# Stage_Driver_v7.net
KiCad netlist of a schematic drawn in EAGLE
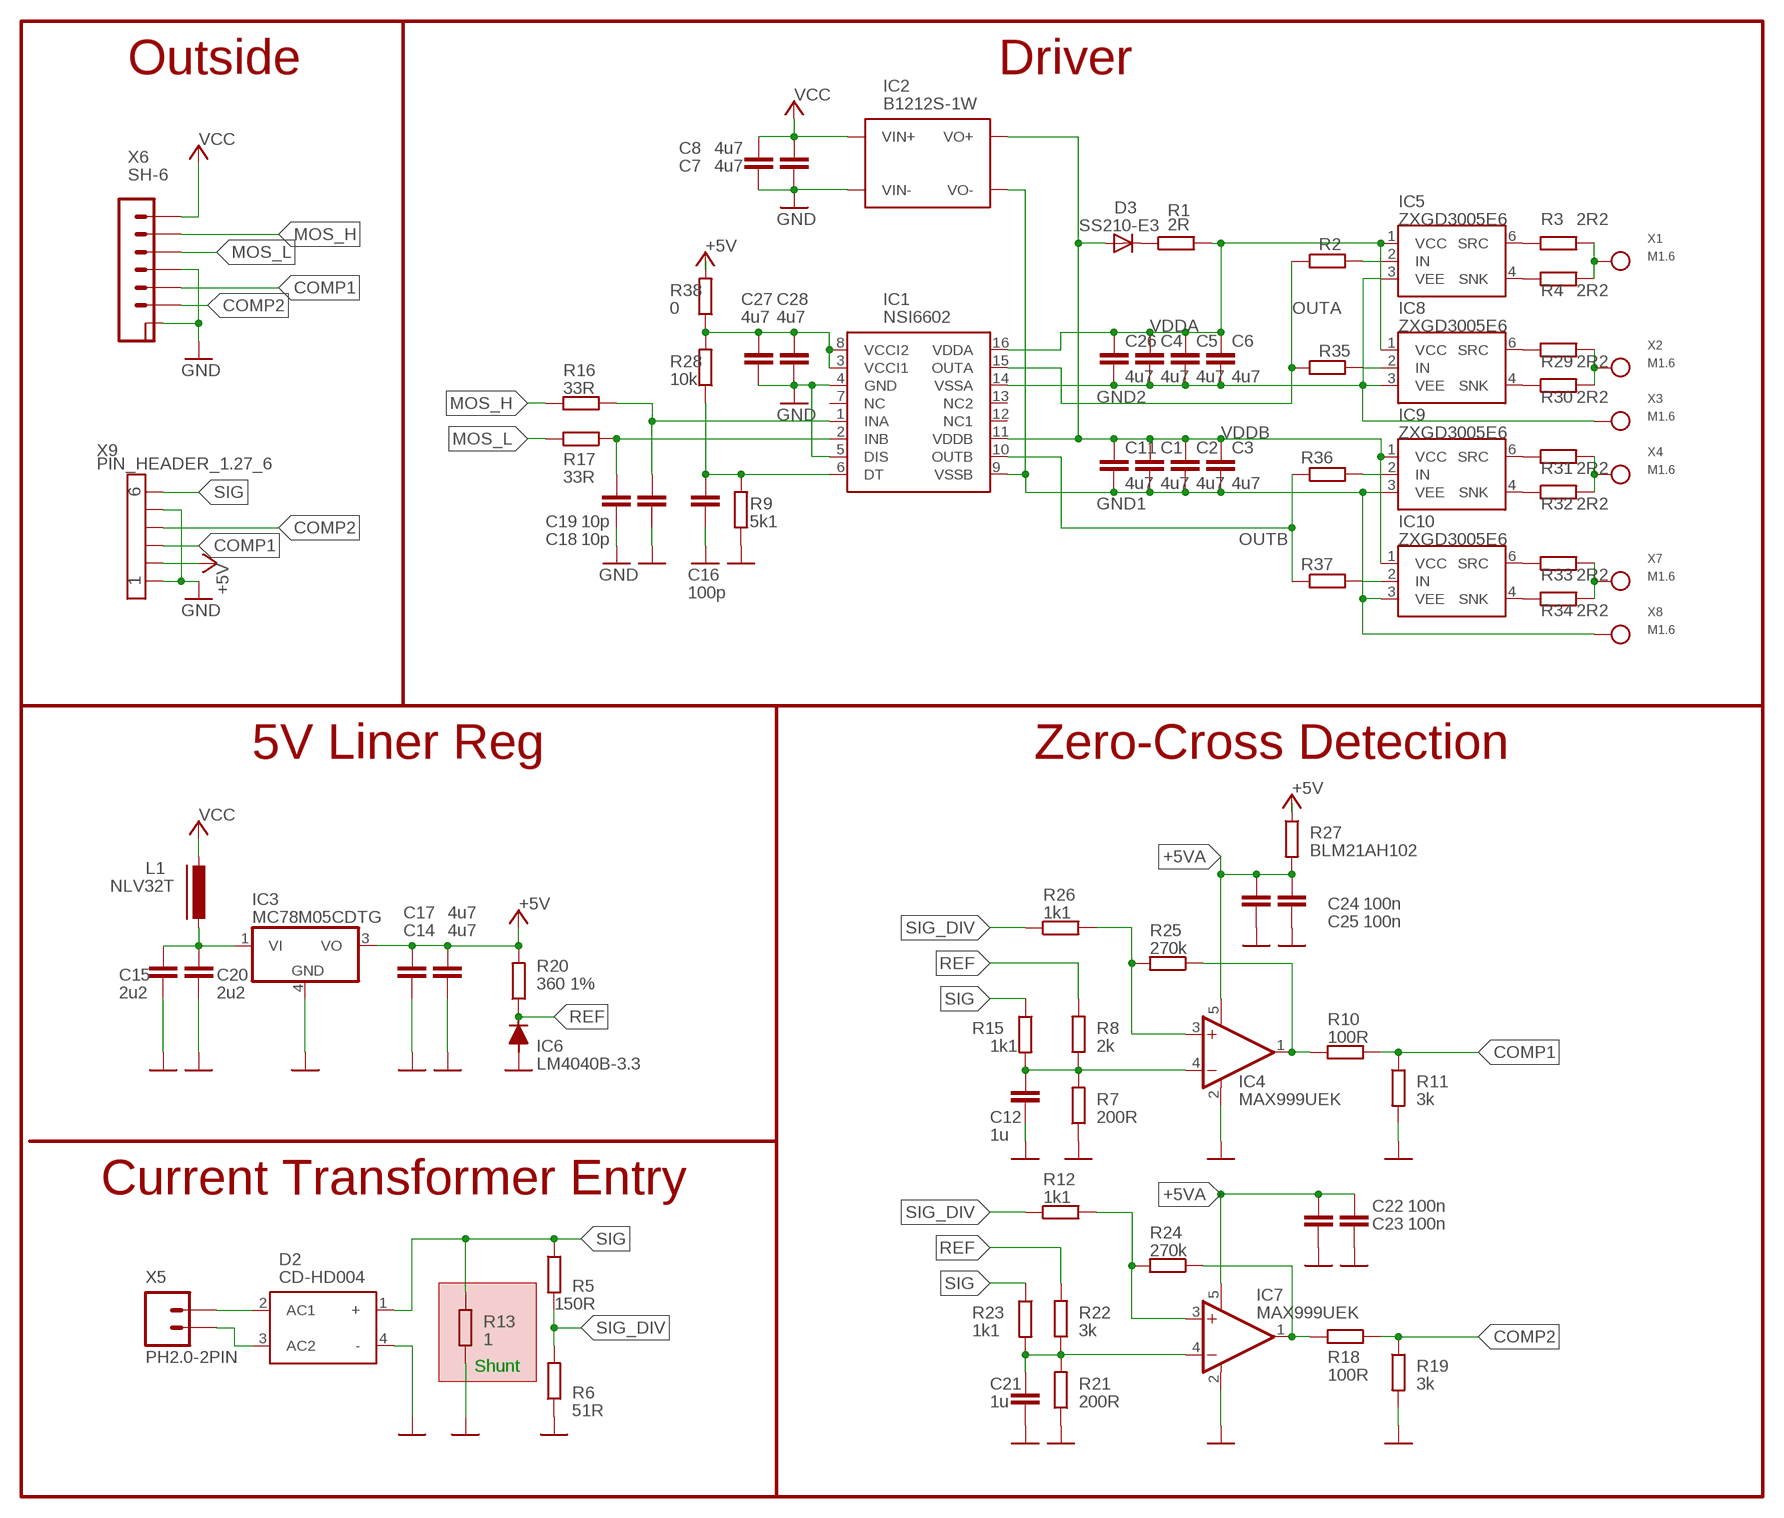
[diagram p0: schematic, sheet 1]

(export (version "E")
  (design (tool "Eeschema 10.0.6"))
  (components
    (comp (ref "C1")
      (value "4u7")
      (footprint "eagle-import:C0805")
      (libsource (lib "eagle-import") (part "C-EUC0805"))
    )
    (comp (ref "C2")
      (value "4u7")
      (footprint "eagle-import:C0805")
      (libsource (lib "eagle-import") (part "C-EUC0805"))
    )
    (comp (ref "C3")
      (value "4u7")
      (footprint "eagle-import:C0805")
      (libsource (lib "eagle-import") (part "C-EUC0805"))
    )
    (comp (ref "C4")
      (value "4u7")
      (footprint "eagle-import:C0805")
      (libsource (lib "eagle-import") (part "C-EUC0805"))
    )
    (comp (ref "C5")
      (value "4u7")
      (footprint "eagle-import:C0805")
      (libsource (lib "eagle-import") (part "C-EUC0805"))
    )
    (comp (ref "C6")
      (value "4u7")
      (footprint "eagle-import:C0805")
      (libsource (lib "eagle-import") (part "C-EUC0805"))
    )
    (comp (ref "C7")
      (value "4u7")
      (footprint "eagle-import:C0805")
      (libsource (lib "eagle-import") (part "C-EUC0805"))
    )
    (comp (ref "C8")
      (value "4u7")
      (footprint "eagle-import:C0805")
      (libsource (lib "eagle-import") (part "C-EUC0805"))
    )
    (comp (ref "C11")
      (value "4u7")
      (footprint "eagle-import:C0805")
      (libsource (lib "eagle-import") (part "C-EUC0805"))
    )
    (comp (ref "C12")
      (value "1u")
      (footprint "eagle-import:C0603")
      (libsource (lib "eagle-import") (part "C-EUC0603"))
    )
    (comp (ref "C14")
      (value "4u7")
      (footprint "eagle-import:C0805")
      (libsource (lib "eagle-import") (part "C-EUC0805"))
    )
    (comp (ref "C15")
      (value "2u2")
      (footprint "eagle-import:C0805")
      (libsource (lib "eagle-import") (part "C-EUC0805"))
    )
    (comp (ref "C16")
      (value "100p")
      (footprint "eagle-import:C0603")
      (libsource (lib "eagle-import") (part "C-EUC0603"))
    )
    (comp (ref "C17")
      (value "4u7")
      (footprint "eagle-import:C0805")
      (libsource (lib "eagle-import") (part "C-EUC0805"))
    )
    (comp (ref "C18")
      (value "10p")
      (footprint "eagle-import:C0603")
      (libsource (lib "eagle-import") (part "C-EUC0603"))
    )
    (comp (ref "C19")
      (value "10p")
      (footprint "eagle-import:C0603")
      (libsource (lib "eagle-import") (part "C-EUC0603"))
    )
    (comp (ref "C20")
      (value "2u2")
      (footprint "eagle-import:C0805")
      (libsource (lib "eagle-import") (part "C-EUC0805"))
    )
    (comp (ref "C21")
      (value "1u")
      (footprint "eagle-import:C0603")
      (libsource (lib "eagle-import") (part "C-EUC0603"))
    )
    (comp (ref "C22")
      (value "100n")
      (footprint "eagle-import:C0603")
      (libsource (lib "eagle-import") (part "C-EUC0603"))
    )
    (comp (ref "C23")
      (value "100n")
      (footprint "eagle-import:C0603")
      (libsource (lib "eagle-import") (part "C-EUC0603"))
    )
    (comp (ref "C24")
      (value "100n")
      (footprint "eagle-import:C0603")
      (libsource (lib "eagle-import") (part "C-EUC0603"))
    )
    (comp (ref "C25")
      (value "100n")
      (footprint "eagle-import:C0603")
      (libsource (lib "eagle-import") (part "C-EUC0603"))
    )
    (comp (ref "C26")
      (value "4u7")
      (footprint "eagle-import:C0805")
      (libsource (lib "eagle-import") (part "C-EUC0805"))
    )
    (comp (ref "C27")
      (value "4u7")
      (footprint "eagle-import:C0603")
      (libsource (lib "eagle-import") (part "C-EUC0603"))
    )
    (comp (ref "C28")
      (value "4u7")
      (footprint "eagle-import:C0603")
      (libsource (lib "eagle-import") (part "C-EUC0603"))
    )
    (comp (ref "D2")
      (value "CD-HD004")
      (footprint "eagle-import:CD-HD0X")
      (libsource (lib "eagle-import") (part "CD-HD004"))
    )
    (comp (ref "D3")
      (value "SS210-E3")
      (footprint "eagle-import:DO-214AA(SMB)")
      (fields
        (field (name "MANUFACTURER_PART_NUMBER") "SS210-E3/5BT")
        (field (name "MOUSER_PART_NUMBER") "625-SS210-E3/5BT")
      )
      (libsource (lib "eagle-import") (part "SS210-E3"))
    )
    (comp (ref "IC1")
      (value "NSI6602")
      (footprint "eagle-import:SOIC16")
      (libsource (lib "eagle-import") (part "NSI6602"))
    )
    (comp (ref "IC2")
      (value "B1212S-1W")
      (footprint "eagle-import:BS-1WR3")
      (libsource (lib "eagle-import") (part "SIM1-XXXX-2"))
    )
    (comp (ref "IC3")
      (value "MC78M05CDTG")
      (footprint "eagle-import:DPACK_3")
      (libsource (lib "eagle-import") (part "MC78M05CDTG"))
    )
    (comp (ref "IC4")
      (value "MAX999UEK")
      (footprint "eagle-import:SOT-23-5")
      (libsource (lib "eagle-import") (part "MAX999UEK"))
    )
    (comp (ref "IC5")
      (value "ZXGD3005E6")
      (footprint "eagle-import:SOT-23-6")
      (libsource (lib "eagle-import") (part "ZXGD3005E6"))
    )
    (comp (ref "IC6")
      (value "LM4040B-3.3")
      (footprint "eagle-import:SOT-23")
      (libsource (lib "eagle-import") (part "LM4040"))
    )
    (comp (ref "IC7")
      (value "MAX999UEK")
      (footprint "eagle-import:SOT-23-5")
      (libsource (lib "eagle-import") (part "MAX999UEK"))
    )
    (comp (ref "IC8")
      (value "ZXGD3005E6")
      (footprint "eagle-import:SOT-23-6")
      (libsource (lib "eagle-import") (part "ZXGD3005E6"))
    )
    (comp (ref "IC9")
      (value "ZXGD3005E6")
      (footprint "eagle-import:SOT-23-6")
      (libsource (lib "eagle-import") (part "ZXGD3005E6"))
    )
    (comp (ref "IC10")
      (value "ZXGD3005E6")
      (footprint "eagle-import:SOT-23-6")
      (libsource (lib "eagle-import") (part "ZXGD3005E6"))
    )
    (comp (ref "L1")
      (value "NLV32T")
      (footprint "eagle-import:NLV32T")
      (libsource (lib "eagle-import") (part "NLV32T"))
    )
    (comp (ref "R1")
      (value "2R")
      (footprint "eagle-import:R1210")
      (libsource (lib "eagle-import") (part "R-EU_R1210"))
    )
    (comp (ref "R2")
      (value "R-EU_R0603")
      (footprint "eagle-import:R0603")
      (libsource (lib "eagle-import") (part "R-EU_R0603"))
    )
    (comp (ref "R3")
      (value "2R2")
      (footprint "eagle-import:R0603")
      (libsource (lib "eagle-import") (part "R-EU_R0603"))
    )
    (comp (ref "R4")
      (value "2R2")
      (footprint "eagle-import:R0603")
      (libsource (lib "eagle-import") (part "R-EU_R0603"))
    )
    (comp (ref "R5")
      (value "150R")
      (footprint "eagle-import:R0805")
      (libsource (lib "eagle-import") (part "R-EU_R0805"))
    )
    (comp (ref "R6")
      (value "51R")
      (footprint "eagle-import:R0805")
      (libsource (lib "eagle-import") (part "R-EU_R0805"))
    )
    (comp (ref "R7")
      (value "200R")
      (footprint "eagle-import:R0603")
      (libsource (lib "eagle-import") (part "R-EU_R0603"))
    )
    (comp (ref "R8")
      (value "2k")
      (footprint "eagle-import:R0603")
      (libsource (lib "eagle-import") (part "R-EU_R0603"))
    )
    (comp (ref "R9")
      (value "5k1")
      (footprint "eagle-import:R0603")
      (libsource (lib "eagle-import") (part "R-EU_R0603"))
    )
    (comp (ref "R10")
      (value "100R")
      (footprint "eagle-import:R0603")
      (libsource (lib "eagle-import") (part "R-EU_R0603"))
    )
    (comp (ref "R11")
      (value "3k")
      (footprint "eagle-import:R0603")
      (libsource (lib "eagle-import") (part "R-EU_R0603"))
    )
    (comp (ref "R12")
      (value "1k1")
      (footprint "eagle-import:R0603")
      (libsource (lib "eagle-import") (part "R-EU_R0603"))
    )
    (comp (ref "R13")
      (value "1")
      (footprint "eagle-import:R1210")
      (libsource (lib "eagle-import") (part "R-EU_R1210"))
    )
    (comp (ref "R15")
      (value "1k1")
      (footprint "eagle-import:R0603")
      (libsource (lib "eagle-import") (part "R-EU_R0603"))
    )
    (comp (ref "R16")
      (value "33R")
      (footprint "eagle-import:R0603")
      (libsource (lib "eagle-import") (part "R-EU_R0603"))
    )
    (comp (ref "R17")
      (value "33R")
      (footprint "eagle-import:R0603")
      (libsource (lib "eagle-import") (part "R-EU_R0603"))
    )
    (comp (ref "R18")
      (value "100R")
      (footprint "eagle-import:R0603")
      (libsource (lib "eagle-import") (part "R-EU_R0603"))
    )
    (comp (ref "R19")
      (value "3k")
      (footprint "eagle-import:R0603")
      (libsource (lib "eagle-import") (part "R-EU_R0603"))
    )
    (comp (ref "R20")
      (value "360 1%")
      (footprint "eagle-import:R0805")
      (libsource (lib "eagle-import") (part "R-EU_R0805"))
    )
    (comp (ref "R21")
      (value "200R")
      (footprint "eagle-import:R0603")
      (libsource (lib "eagle-import") (part "R-EU_R0603"))
    )
    (comp (ref "R22")
      (value "3k")
      (footprint "eagle-import:R0603")
      (libsource (lib "eagle-import") (part "R-EU_R0603"))
    )
    (comp (ref "R23")
      (value "1k1")
      (footprint "eagle-import:R0603")
      (libsource (lib "eagle-import") (part "R-EU_R0603"))
    )
    (comp (ref "R24")
      (value "270k")
      (footprint "eagle-import:R0603")
      (libsource (lib "eagle-import") (part "R-EU_R0603"))
    )
    (comp (ref "R25")
      (value "270k")
      (footprint "eagle-import:R0603")
      (libsource (lib "eagle-import") (part "R-EU_R0603"))
    )
    (comp (ref "R26")
      (value "1k1")
      (footprint "eagle-import:R0603")
      (libsource (lib "eagle-import") (part "R-EU_R0603"))
    )
    (comp (ref "R27")
      (value "BLM21AH102")
      (footprint "eagle-import:R0805")
      (libsource (lib "eagle-import") (part "R-EU_R0805"))
    )
    (comp (ref "R28")
      (value "10k")
      (footprint "eagle-import:R0603")
      (libsource (lib "eagle-import") (part "R-EU_R0603"))
    )
    (comp (ref "R29")
      (value "2R2")
      (footprint "eagle-import:R0603")
      (libsource (lib "eagle-import") (part "R-EU_R0603"))
    )
    (comp (ref "R30")
      (value "2R2")
      (footprint "eagle-import:R0603")
      (libsource (lib "eagle-import") (part "R-EU_R0603"))
    )
    (comp (ref "R31")
      (value "2R2")
      (footprint "eagle-import:R0603")
      (libsource (lib "eagle-import") (part "R-EU_R0603"))
    )
    (comp (ref "R32")
      (value "2R2")
      (footprint "eagle-import:R0603")
      (libsource (lib "eagle-import") (part "R-EU_R0603"))
    )
    (comp (ref "R33")
      (value "2R2")
      (footprint "eagle-import:R0603")
      (libsource (lib "eagle-import") (part "R-EU_R0603"))
    )
    (comp (ref "R34")
      (value "2R2")
      (footprint "eagle-import:R0603")
      (libsource (lib "eagle-import") (part "R-EU_R0603"))
    )
    (comp (ref "R35")
      (value "R-EU_R0603")
      (footprint "eagle-import:R0603")
      (libsource (lib "eagle-import") (part "R-EU_R0603"))
    )
    (comp (ref "R36")
      (value "R-EU_R0603")
      (footprint "eagle-import:R0603")
      (libsource (lib "eagle-import") (part "R-EU_R0603"))
    )
    (comp (ref "R37")
      (value "R-EU_R0603")
      (footprint "eagle-import:R0603")
      (libsource (lib "eagle-import") (part "R-EU_R0603"))
    )
    (comp (ref "R38")
      (value "0")
      (footprint "eagle-import:R0805")
      (libsource (lib "eagle-import") (part "R-EU_R0805"))
    )
    (comp (ref "X1")
      (value "M1.6")
      (footprint "eagle-import:M1.6")
      (libsource (lib "eagle-import") (part "M1.6"))
    )
    (comp (ref "X2")
      (value "M1.6")
      (footprint "eagle-import:M1.6")
      (libsource (lib "eagle-import") (part "M1.6"))
    )
    (comp (ref "X3")
      (value "M1.6")
      (footprint "eagle-import:M1.6")
      (libsource (lib "eagle-import") (part "M1.6"))
    )
    (comp (ref "X4")
      (value "M1.6")
      (footprint "eagle-import:M1.6")
      (libsource (lib "eagle-import") (part "M1.6"))
    )
    (comp (ref "X5")
      (value "PH2.0-2PIN")
      (footprint "eagle-import:PH2.0-2PIN")
      (libsource (lib "eagle-import") (part "PH2.0-2PIN"))
    )
    (comp (ref "X6")
      (value "SH-6")
      (footprint "eagle-import:SH-6")
      (libsource (lib "eagle-import") (part "SH-6"))
    )
    (comp (ref "X7")
      (value "M1.6")
      (footprint "eagle-import:M1.6")
      (libsource (lib "eagle-import") (part "M1.6"))
    )
    (comp (ref "X8")
      (value "M1.6")
      (footprint "eagle-import:M1.6")
      (libsource (lib "eagle-import") (part "M1.6"))
    )
    (comp (ref "X9")
      (value "PIN_HEADER_1.27_6")
      (footprint "eagle-import:PIN_HEADER_1.27_6")
      (libsource (lib "eagle-import") (part "PIN_HEADER_1.27_6"))
    )
  )
  (nets
    (net (code "1") (name "+5V") (class "Default")
      (node (ref "C14") (pin "1") (pinfunction "1_1") (pintype "passive"))
      (node (ref "C17") (pin "1") (pinfunction "1_1") (pintype "passive"))
      (node (ref "IC3") (pin "3") (pinfunction "VO_3") (pintype "passive"))
      (node (ref "R20") (pin "2") (pinfunction "2_2") (pintype "passive"))
      (node (ref "R27") (pin "1") (pinfunction "1_1") (pintype "passive"))
      (node (ref "R38") (pin "2") (pinfunction "2_2") (pintype "passive"))
      (node (ref "X9") (pin "P$2") (pinfunction "P$2_P$2") (pintype "bidirectional"))
    )
    (net (code "2") (name "+5VA") (class "Default")
      (node (ref "C22") (pin "1") (pinfunction "1_1") (pintype "passive"))
      (node (ref "C23") (pin "1") (pinfunction "1_1") (pintype "passive"))
      (node (ref "C24") (pin "1") (pinfunction "1_1") (pintype "passive"))
      (node (ref "C25") (pin "1") (pinfunction "1_1") (pintype "passive"))
      (node (ref "IC4") (pin "5") (pinfunction "V+_5") (pintype "power_in"))
      (node (ref "IC7") (pin "5") (pinfunction "V+_5") (pintype "power_in"))
      (node (ref "R27") (pin "2") (pinfunction "2_2") (pintype "passive"))
    )
    (net (code "3") (name "/GND1") (class "Default")
      (node (ref "C1") (pin "2") (pinfunction "2_2") (pintype "passive"))
      (node (ref "C11") (pin "2") (pinfunction "2_2") (pintype "passive"))
      (node (ref "C2") (pin "2") (pinfunction "2_2") (pintype "passive"))
      (node (ref "C3") (pin "2") (pinfunction "2_2") (pintype "passive"))
      (node (ref "IC1") (pin "9") (pinfunction "VSSB_9") (pintype "bidirectional"))
      (node (ref "IC10") (pin "3") (pinfunction "VEE_3") (pintype "bidirectional"))
      (node (ref "IC2") (pin "P$3") (pinfunction "VO-_P$3") (pintype "bidirectional"))
      (node (ref "IC9") (pin "3") (pinfunction "VEE_3") (pintype "bidirectional"))
      (node (ref "X8") (pin "P$1") (pinfunction "P$1_P$1") (pintype "bidirectional"))
    )
    (net (code "4") (name "/GND2") (class "Default")
      (node (ref "C26") (pin "2") (pinfunction "2_2") (pintype "passive"))
      (node (ref "C4") (pin "2") (pinfunction "2_2") (pintype "passive"))
      (node (ref "C5") (pin "2") (pinfunction "2_2") (pintype "passive"))
      (node (ref "C6") (pin "2") (pinfunction "2_2") (pintype "passive"))
      (node (ref "IC1") (pin "14") (pinfunction "VSSA_14") (pintype "bidirectional"))
      (node (ref "IC5") (pin "3") (pinfunction "VEE_3") (pintype "bidirectional"))
      (node (ref "IC8") (pin "3") (pinfunction "VEE_3") (pintype "bidirectional"))
      (node (ref "X3") (pin "P$1") (pinfunction "P$1_P$1") (pintype "bidirectional"))
    )
    (net (code "5") (name "/OUTA") (class "Default")
      (node (ref "IC1") (pin "15") (pinfunction "OUTA_15") (pintype "bidirectional"))
      (node (ref "R2") (pin "1") (pinfunction "1_1") (pintype "passive"))
      (node (ref "R35") (pin "1") (pinfunction "1_1") (pintype "passive"))
    )
    (net (code "6") (name "/OUTB") (class "Default")
      (node (ref "IC1") (pin "10") (pinfunction "OUTB_10") (pintype "bidirectional"))
      (node (ref "R36") (pin "1") (pinfunction "1_1") (pintype "passive"))
      (node (ref "R37") (pin "1") (pinfunction "1_1") (pintype "passive"))
    )
    (net (code "7") (name "/VDDA") (class "Default")
      (node (ref "C26") (pin "1") (pinfunction "1_1") (pintype "passive"))
      (node (ref "C4") (pin "1") (pinfunction "1_1") (pintype "passive"))
      (node (ref "C5") (pin "1") (pinfunction "1_1") (pintype "passive"))
      (node (ref "C6") (pin "1") (pinfunction "1_1") (pintype "passive"))
      (node (ref "IC1") (pin "16") (pinfunction "VDDA_16") (pintype "bidirectional"))
      (node (ref "IC5") (pin "1") (pinfunction "VCC_1") (pintype "bidirectional"))
      (node (ref "IC8") (pin "1") (pinfunction "VCC_1") (pintype "bidirectional"))
      (node (ref "R1") (pin "2") (pinfunction "2_2") (pintype "passive"))
    )
    (net (code "8") (name "/VDDB") (class "Default")
      (node (ref "C1") (pin "1") (pinfunction "1_1") (pintype "passive"))
      (node (ref "C11") (pin "1") (pinfunction "1_1") (pintype "passive"))
      (node (ref "C2") (pin "1") (pinfunction "1_1") (pintype "passive"))
      (node (ref "C3") (pin "1") (pinfunction "1_1") (pintype "passive"))
      (node (ref "D3") (pin "2") (pinfunction "A_2") (pintype "passive"))
      (node (ref "IC1") (pin "11") (pinfunction "VDDB_11") (pintype "bidirectional"))
      (node (ref "IC10") (pin "1") (pinfunction "VCC_1") (pintype "bidirectional"))
      (node (ref "IC2") (pin "P$4") (pinfunction "VO+_P$4") (pintype "bidirectional"))
      (node (ref "IC9") (pin "1") (pinfunction "VCC_1") (pintype "bidirectional"))
    )
    (net (code "9") (name "COMP1") (class "Default")
      (node (ref "R10") (pin "1") (pinfunction "1_1") (pintype "passive"))
      (node (ref "R11") (pin "1") (pinfunction "1_1") (pintype "passive"))
      (node (ref "X6") (pin "P$5") (pinfunction "5_P$5") (pintype "passive"))
      (node (ref "X9") (pin "P$3") (pinfunction "P$3_P$3") (pintype "bidirectional"))
    )
    (net (code "10") (name "COMP2") (class "Default")
      (node (ref "R18") (pin "1") (pinfunction "1_1") (pintype "passive"))
      (node (ref "R19") (pin "1") (pinfunction "1_1") (pintype "passive"))
      (node (ref "X6") (pin "P$6") (pinfunction "6_P$6") (pintype "passive"))
      (node (ref "X9") (pin "P$4") (pinfunction "P$4_P$4") (pintype "bidirectional"))
    )
    (net (code "11") (name "GND") (class "Default")
      (node (ref "C12") (pin "2") (pinfunction "2_2") (pintype "passive"))
      (node (ref "C14") (pin "2") (pinfunction "2_2") (pintype "passive"))
      (node (ref "C15") (pin "2") (pinfunction "2_2") (pintype "passive"))
      (node (ref "C16") (pin "2") (pinfunction "2_2") (pintype "passive"))
      (node (ref "C17") (pin "2") (pinfunction "2_2") (pintype "passive"))
      (node (ref "C18") (pin "2") (pinfunction "2_2") (pintype "passive"))
      (node (ref "C19") (pin "2") (pinfunction "2_2") (pintype "passive"))
      (node (ref "C20") (pin "2") (pinfunction "2_2") (pintype "passive"))
      (node (ref "C21") (pin "2") (pinfunction "2_2") (pintype "passive"))
      (node (ref "C22") (pin "2") (pinfunction "2_2") (pintype "passive"))
      (node (ref "C23") (pin "2") (pinfunction "2_2") (pintype "passive"))
      (node (ref "C24") (pin "2") (pinfunction "2_2") (pintype "passive"))
      (node (ref "C25") (pin "2") (pinfunction "2_2") (pintype "passive"))
      (node (ref "C27") (pin "2") (pinfunction "2_2") (pintype "passive"))
      (node (ref "C28") (pin "2") (pinfunction "2_2") (pintype "passive"))
      (node (ref "C7") (pin "2") (pinfunction "2_2") (pintype "passive"))
      (node (ref "C8") (pin "2") (pinfunction "2_2") (pintype "passive"))
      (node (ref "D2") (pin "4") (pinfunction "-_4") (pintype "bidirectional"))
      (node (ref "IC1") (pin "4") (pinfunction "GND_4") (pintype "bidirectional"))
      (node (ref "IC1") (pin "5") (pinfunction "DIS_5") (pintype "bidirectional"))
      (node (ref "IC2") (pin "P$1") (pinfunction "VIN-_P$1") (pintype "bidirectional"))
      (node (ref "IC3") (pin "4") (pinfunction "GND_4") (pintype "passive"))
      (node (ref "IC4") (pin "2") (pinfunction "V-_2") (pintype "power_in"))
      (node (ref "IC6") (pin "2") (pinfunction "A_2") (pintype "passive"))
      (node (ref "IC7") (pin "2") (pinfunction "V-_2") (pintype "power_in"))
      (node (ref "R11") (pin "2") (pinfunction "2_2") (pintype "passive"))
      (node (ref "R13") (pin "1") (pinfunction "1_1") (pintype "passive"))
      (node (ref "R19") (pin "2") (pinfunction "2_2") (pintype "passive"))
      (node (ref "R21") (pin "1") (pinfunction "1_1") (pintype "passive"))
      (node (ref "R6") (pin "1") (pinfunction "1_1") (pintype "passive"))
      (node (ref "R7") (pin "1") (pinfunction "1_1") (pintype "passive"))
      (node (ref "R9") (pin "1") (pinfunction "1_1") (pintype "passive"))
      (node (ref "X6") (pin "G1") (pinfunction "G_G1") (pintype "bidirectional"))
      (node (ref "X6") (pin "G2") (pinfunction "G_G2") (pintype "bidirectional"))
      (node (ref "X6") (pin "P$4") (pinfunction "4_P$4") (pintype "passive"))
      (node (ref "X9") (pin "P$1") (pinfunction "P$1_P$1") (pintype "bidirectional"))
      (node (ref "X9") (pin "P$5") (pinfunction "P$5_P$5") (pintype "bidirectional"))
    )
    (net (code "12") (name "MOS_H") (class "Default")
      (node (ref "R16") (pin "2") (pinfunction "2_2") (pintype "passive"))
      (node (ref "X6") (pin "P$2") (pinfunction "2_P$2") (pintype "passive"))
    )
    (net (code "13") (name "MOS_L") (class "Default")
      (node (ref "R17") (pin "2") (pinfunction "2_2") (pintype "passive"))
      (node (ref "X6") (pin "P$3") (pinfunction "3_P$3") (pintype "passive"))
    )
    (net (code "14") (name "Net-(D2-AC1)") (class "Default")
      (node (ref "D2") (pin "2") (pinfunction "AC1_2") (pintype "bidirectional"))
      (node (ref "X5") (pin "P$2") (pinfunction "2_P$2") (pintype "passive"))
    )
    (net (code "15") (name "Net-(D2-AC2)") (class "Default")
      (node (ref "D2") (pin "3") (pinfunction "AC2_3") (pintype "bidirectional"))
      (node (ref "X5") (pin "P$1") (pinfunction "1_P$1") (pintype "passive"))
    )
    (net (code "16") (name "Net-(D3-C)") (class "Default")
      (node (ref "D3") (pin "1") (pinfunction "C_1") (pintype "passive"))
      (node (ref "R1") (pin "1") (pinfunction "1_1") (pintype "passive"))
    )
    (net (code "17") (name "Net-(IC1-DT)") (class "Default")
      (node (ref "C16") (pin "1") (pinfunction "1_1") (pintype "passive"))
      (node (ref "IC1") (pin "6") (pinfunction "DT_6") (pintype "bidirectional"))
      (node (ref "R28") (pin "1") (pinfunction "1_1") (pintype "passive"))
      (node (ref "R9") (pin "2") (pinfunction "2_2") (pintype "passive"))
    )
    (net (code "18") (name "Net-(IC1-INA)") (class "Default")
      (node (ref "C18") (pin "1") (pinfunction "1_1") (pintype "passive"))
      (node (ref "IC1") (pin "1") (pinfunction "INA_1") (pintype "bidirectional"))
      (node (ref "R16") (pin "1") (pinfunction "1_1") (pintype "passive"))
    )
    (net (code "19") (name "Net-(IC1-INB)") (class "Default")
      (node (ref "C19") (pin "1") (pinfunction "1_1") (pintype "passive"))
      (node (ref "IC1") (pin "2") (pinfunction "INB_2") (pintype "bidirectional"))
      (node (ref "R17") (pin "1") (pinfunction "1_1") (pintype "passive"))
    )
    (net (code "20") (name "Net-(IC1-VCCI1)") (class "Default")
      (node (ref "C27") (pin "1") (pinfunction "1_1") (pintype "passive"))
      (node (ref "C28") (pin "1") (pinfunction "1_1") (pintype "passive"))
      (node (ref "IC1") (pin "3") (pinfunction "VCCI1_3") (pintype "bidirectional"))
      (node (ref "IC1") (pin "8") (pinfunction "VCCI2_8") (pintype "bidirectional"))
      (node (ref "R28") (pin "2") (pinfunction "2_2") (pintype "passive"))
      (node (ref "R38") (pin "1") (pinfunction "1_1") (pintype "passive"))
    )
    (net (code "21") (name "Net-(IC3-VI)") (class "Default")
      (node (ref "C15") (pin "1") (pinfunction "1_1") (pintype "passive"))
      (node (ref "C20") (pin "1") (pinfunction "1_1") (pintype "passive"))
      (node (ref "IC3") (pin "1") (pinfunction "VI_1") (pintype "input"))
      (node (ref "L1") (pin "P$1") (pinfunction "1_P$1") (pintype "passive"))
    )
    (net (code "22") (name "Net-(IC4-+IN)") (class "Default")
      (node (ref "IC4") (pin "3") (pinfunction "+IN_3") (pintype "input"))
      (node (ref "R25") (pin "2") (pinfunction "2_2") (pintype "passive"))
      (node (ref "R26") (pin "2") (pinfunction "2_2") (pintype "passive"))
    )
    (net (code "23") (name "Net-(IC4--IN)") (class "Default")
      (node (ref "C12") (pin "1") (pinfunction "1_1") (pintype "passive"))
      (node (ref "IC4") (pin "4") (pinfunction "-IN_4") (pintype "input"))
      (node (ref "R15") (pin "2") (pinfunction "2_2") (pintype "passive"))
      (node (ref "R7") (pin "2") (pinfunction "2_2") (pintype "passive"))
      (node (ref "R8") (pin "1") (pinfunction "1_1") (pintype "passive"))
    )
    (net (code "24") (name "Net-(IC4-OUT)") (class "Default")
      (node (ref "IC4") (pin "1") (pinfunction "OUT_1") (pintype "output"))
      (node (ref "R10") (pin "2") (pinfunction "2_2") (pintype "passive"))
      (node (ref "R25") (pin "1") (pinfunction "1_1") (pintype "passive"))
    )
    (net (code "25") (name "Net-(IC5-IN)") (class "Default")
      (node (ref "IC5") (pin "2") (pinfunction "IN_2") (pintype "bidirectional"))
      (node (ref "R2") (pin "2") (pinfunction "2_2") (pintype "passive"))
    )
    (net (code "26") (name "Net-(IC5-SNK)") (class "Default")
      (node (ref "IC5") (pin "4") (pinfunction "SNK_4") (pintype "bidirectional"))
      (node (ref "R4") (pin "1") (pinfunction "1_1") (pintype "passive"))
    )
    (net (code "27") (name "Net-(IC5-SRC)") (class "Default")
      (node (ref "IC5") (pin "6") (pinfunction "SRC_6") (pintype "bidirectional"))
      (node (ref "R3") (pin "1") (pinfunction "1_1") (pintype "passive"))
    )
    (net (code "28") (name "Net-(IC7-+IN)") (class "Default")
      (node (ref "IC7") (pin "3") (pinfunction "+IN_3") (pintype "input"))
      (node (ref "R12") (pin "2") (pinfunction "2_2") (pintype "passive"))
      (node (ref "R24") (pin "2") (pinfunction "2_2") (pintype "passive"))
    )
    (net (code "29") (name "Net-(IC7--IN)") (class "Default")
      (node (ref "C21") (pin "1") (pinfunction "1_1") (pintype "passive"))
      (node (ref "IC7") (pin "4") (pinfunction "-IN_4") (pintype "input"))
      (node (ref "R21") (pin "2") (pinfunction "2_2") (pintype "passive"))
      (node (ref "R22") (pin "1") (pinfunction "1_1") (pintype "passive"))
      (node (ref "R23") (pin "2") (pinfunction "2_2") (pintype "passive"))
    )
    (net (code "30") (name "Net-(IC7-OUT)") (class "Default")
      (node (ref "IC7") (pin "1") (pinfunction "OUT_1") (pintype "output"))
      (node (ref "R18") (pin "2") (pinfunction "2_2") (pintype "passive"))
      (node (ref "R24") (pin "1") (pinfunction "1_1") (pintype "passive"))
    )
    (net (code "31") (name "Net-(IC8-IN)") (class "Default")
      (node (ref "IC8") (pin "2") (pinfunction "IN_2") (pintype "bidirectional"))
      (node (ref "R35") (pin "2") (pinfunction "2_2") (pintype "passive"))
    )
    (net (code "32") (name "Net-(IC8-SNK)") (class "Default")
      (node (ref "IC8") (pin "4") (pinfunction "SNK_4") (pintype "bidirectional"))
      (node (ref "R30") (pin "1") (pinfunction "1_1") (pintype "passive"))
    )
    (net (code "33") (name "Net-(IC8-SRC)") (class "Default")
      (node (ref "IC8") (pin "6") (pinfunction "SRC_6") (pintype "bidirectional"))
      (node (ref "R29") (pin "1") (pinfunction "1_1") (pintype "passive"))
    )
    (net (code "34") (name "Net-(IC9-IN)") (class "Default")
      (node (ref "IC9") (pin "2") (pinfunction "IN_2") (pintype "bidirectional"))
      (node (ref "R36") (pin "2") (pinfunction "2_2") (pintype "passive"))
    )
    (net (code "35") (name "Net-(IC9-SNK)") (class "Default")
      (node (ref "IC9") (pin "4") (pinfunction "SNK_4") (pintype "bidirectional"))
      (node (ref "R32") (pin "1") (pinfunction "1_1") (pintype "passive"))
    )
    (net (code "36") (name "Net-(IC9-SRC)") (class "Default")
      (node (ref "IC9") (pin "6") (pinfunction "SRC_6") (pintype "bidirectional"))
      (node (ref "R31") (pin "1") (pinfunction "1_1") (pintype "passive"))
    )
    (net (code "37") (name "Net-(IC10-IN)") (class "Default")
      (node (ref "IC10") (pin "2") (pinfunction "IN_2") (pintype "bidirectional"))
      (node (ref "R37") (pin "2") (pinfunction "2_2") (pintype "passive"))
    )
    (net (code "38") (name "Net-(IC10-SNK)") (class "Default")
      (node (ref "IC10") (pin "4") (pinfunction "SNK_4") (pintype "bidirectional"))
      (node (ref "R34") (pin "1") (pinfunction "1_1") (pintype "passive"))
    )
    (net (code "39") (name "Net-(IC10-SRC)") (class "Default")
      (node (ref "IC10") (pin "6") (pinfunction "SRC_6") (pintype "bidirectional"))
      (node (ref "R33") (pin "1") (pinfunction "1_1") (pintype "passive"))
    )
    (net (code "40") (name "Net-(R3-Pad2)") (class "Default")
      (node (ref "R3") (pin "2") (pinfunction "2_2") (pintype "passive"))
      (node (ref "R4") (pin "2") (pinfunction "2_2") (pintype "passive"))
      (node (ref "X1") (pin "P$1") (pinfunction "P$1_P$1") (pintype "bidirectional"))
    )
    (net (code "41") (name "Net-(R29-Pad2)") (class "Default")
      (node (ref "R29") (pin "2") (pinfunction "2_2") (pintype "passive"))
      (node (ref "R30") (pin "2") (pinfunction "2_2") (pintype "passive"))
      (node (ref "X2") (pin "P$1") (pinfunction "P$1_P$1") (pintype "bidirectional"))
    )
    (net (code "42") (name "Net-(R31-Pad2)") (class "Default")
      (node (ref "R31") (pin "2") (pinfunction "2_2") (pintype "passive"))
      (node (ref "R32") (pin "2") (pinfunction "2_2") (pintype "passive"))
      (node (ref "X4") (pin "P$1") (pinfunction "P$1_P$1") (pintype "bidirectional"))
    )
    (net (code "43") (name "Net-(R33-Pad2)") (class "Default")
      (node (ref "R33") (pin "2") (pinfunction "2_2") (pintype "passive"))
      (node (ref "R34") (pin "2") (pinfunction "2_2") (pintype "passive"))
      (node (ref "X7") (pin "P$1") (pinfunction "P$1_P$1") (pintype "bidirectional"))
    )
    (net (code "44") (name "REF") (class "Default")
      (node (ref "IC6") (pin "1") (pinfunction "K_1") (pintype "passive"))
      (node (ref "R20") (pin "1") (pinfunction "1_1") (pintype "passive"))
      (node (ref "R22") (pin "2") (pinfunction "2_2") (pintype "passive"))
      (node (ref "R8") (pin "2") (pinfunction "2_2") (pintype "passive"))
    )
    (net (code "45") (name "SIG") (class "Default")
      (node (ref "D2") (pin "1") (pinfunction "+_1") (pintype "bidirectional"))
      (node (ref "R13") (pin "2") (pinfunction "2_2") (pintype "passive"))
      (node (ref "R15") (pin "1") (pinfunction "1_1") (pintype "passive"))
      (node (ref "R23") (pin "1") (pinfunction "1_1") (pintype "passive"))
      (node (ref "R5") (pin "1") (pinfunction "1_1") (pintype "passive"))
      (node (ref "X9") (pin "P$6") (pinfunction "P$6_P$6") (pintype "bidirectional"))
    )
    (net (code "46") (name "SIG_DIV") (class "Default")
      (node (ref "R12") (pin "1") (pinfunction "1_1") (pintype "passive"))
      (node (ref "R26") (pin "1") (pinfunction "1_1") (pintype "passive"))
      (node (ref "R5") (pin "2") (pinfunction "2_2") (pintype "passive"))
      (node (ref "R6") (pin "2") (pinfunction "2_2") (pintype "passive"))
    )
    (net (code "47") (name "VCC") (class "Default")
      (node (ref "C7") (pin "1") (pinfunction "1_1") (pintype "passive"))
      (node (ref "C8") (pin "1") (pinfunction "1_1") (pintype "passive"))
      (node (ref "IC2") (pin "P$2") (pinfunction "VIN+_P$2") (pintype "bidirectional"))
      (node (ref "L1") (pin "P$2") (pinfunction "2_P$2") (pintype "passive"))
      (node (ref "X6") (pin "P$1") (pinfunction "1_P$1") (pintype "passive"))
    )
    (net (code "48") (name "unconnected-(IC1-NC-Pad7)") (class "Default")
      (node (ref "IC1") (pin "7") (pinfunction "NC_7") (pintype "bidirectional"))
    )
    (net (code "49") (name "unconnected-(IC1-NC1-Pad12)") (class "Default")
      (node (ref "IC1") (pin "12") (pinfunction "NC1_12") (pintype "bidirectional"))
    )
    (net (code "50") (name "unconnected-(IC1-NC2-Pad13)") (class "Default")
      (node (ref "IC1") (pin "13") (pinfunction "NC2_13") (pintype "bidirectional"))
    )
  )
)
